# ATmega16A.net
KiCad netlist of a schematic drawn in EAGLE
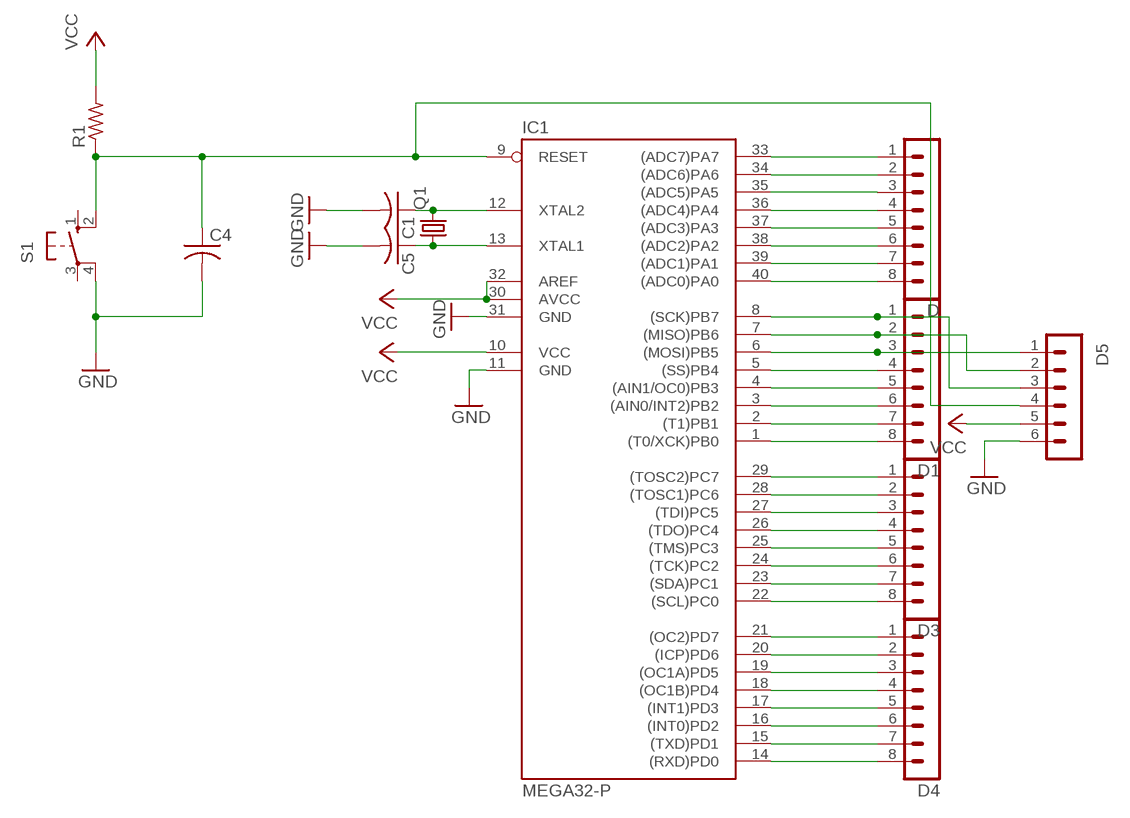
[diagram p0: schematic, sheet 1]

(export (version "E")
  (design (tool "Eeschema 10.0.6"))
  (components
    (comp (ref "C1")
      (value "C-US025-025X050")
      (footprint "eagle-import:C025-025X050")
      (libsource (lib "eagle-import") (part "C-US025-025X050"))
    )
    (comp (ref "C4")
      (value "C-US025-025X050")
      (footprint "eagle-import:C025-025X050")
      (libsource (lib "eagle-import") (part "C-US025-025X050"))
    )
    (comp (ref "C5")
      (value "C-US025-025X050")
      (footprint "eagle-import:C025-025X050")
      (libsource (lib "eagle-import") (part "C-US025-025X050"))
    )
    (comp (ref "D")
      (value "MA08-1")
      (footprint "eagle-import:MA08-1")
      (libsource (lib "eagle-import") (part "MA08-1"))
    )
    (comp (ref "D1")
      (value "MA08-1")
      (footprint "eagle-import:MA08-1")
      (libsource (lib "eagle-import") (part "MA08-1"))
    )
    (comp (ref "D3")
      (value "MA08-1")
      (footprint "eagle-import:MA08-1")
      (libsource (lib "eagle-import") (part "MA08-1"))
    )
    (comp (ref "D4")
      (value "MA08-1")
      (footprint "eagle-import:MA08-1")
      (libsource (lib "eagle-import") (part "MA08-1"))
    )
    (comp (ref "D5")
      (value "MA06-1")
      (footprint "eagle-import:MA06-1")
      (libsource (lib "eagle-import") (part "MA06-1"))
    )
    (comp (ref "IC1")
      (value "MEGA32-P")
      (footprint "eagle-import:DIL40")
      (fields (field (name "MPN") "ATMEGA32-16PU"))
      (libsource (lib "eagle-import") (part "MEGA32-P"))
    )
    (comp (ref "Q1")
      (value "CRYSTALHC49S")
      (footprint "eagle-import:HC49_S")
      (libsource (lib "eagle-import") (part "CRYSTALHC49S"))
    )
    (comp (ref "R1")
      (value "R-US_0204/7")
      (footprint "eagle-import:0204_7")
      (libsource (lib "eagle-import") (part "R-US_0204/7"))
    )
    (comp (ref "S1")
      (value "10-XX")
      (footprint "eagle-import:B3F-10XX")
      (fields (field (name "MPN") "B3F-1000"))
      (libsource (lib "eagle-import") (part "10-XX"))
    )
  )
  (nets
    (net (code "1") (name "GND") (class "Default")
      (node (ref "C1") (pin "2") (pinfunction "2_2") (pintype "passive"))
      (node (ref "C4") (pin "2") (pinfunction "2_2") (pintype "passive"))
      (node (ref "C5") (pin "2") (pinfunction "2_2") (pintype "passive"))
      (node (ref "D5") (pin "6") (pinfunction "6_6") (pintype "passive"))
      (node (ref "IC1") (pin "11") (pinfunction "GND_11") (pintype "power_in"))
      (node (ref "IC1") (pin "31") (pinfunction "GND_31") (pintype "power_in"))
      (node (ref "S1") (pin "4") (pinfunction "P1_4") (pintype "passive"))
    )
    (net (code "2") (name "Net-(IC1-(ADC0)PA0)") (class "Default")
      (node (ref "D") (pin "8") (pinfunction "8_8") (pintype "passive"))
      (node (ref "IC1") (pin "40") (pinfunction "(ADC0)PA0_40") (pintype "bidirectional"))
    )
    (net (code "3") (name "Net-(IC1-(ADC1)PA1)") (class "Default")
      (node (ref "D") (pin "7") (pinfunction "7_7") (pintype "passive"))
      (node (ref "IC1") (pin "39") (pinfunction "(ADC1)PA1_39") (pintype "bidirectional"))
    )
    (net (code "4") (name "Net-(IC1-(ADC2)PA2)") (class "Default")
      (node (ref "D") (pin "6") (pinfunction "6_6") (pintype "passive"))
      (node (ref "IC1") (pin "38") (pinfunction "(ADC2)PA2_38") (pintype "bidirectional"))
    )
    (net (code "5") (name "Net-(IC1-(ADC3)PA3)") (class "Default")
      (node (ref "D") (pin "5") (pinfunction "5_5") (pintype "passive"))
      (node (ref "IC1") (pin "37") (pinfunction "(ADC3)PA3_37") (pintype "bidirectional"))
    )
    (net (code "6") (name "Net-(IC1-(ADC4)PA4)") (class "Default")
      (node (ref "D") (pin "4") (pinfunction "4_4") (pintype "passive"))
      (node (ref "IC1") (pin "36") (pinfunction "(ADC4)PA4_36") (pintype "bidirectional"))
    )
    (net (code "7") (name "Net-(IC1-(ADC5)PA5)") (class "Default")
      (node (ref "D") (pin "3") (pinfunction "3_3") (pintype "passive"))
      (node (ref "IC1") (pin "35") (pinfunction "(ADC5)PA5_35") (pintype "bidirectional"))
    )
    (net (code "8") (name "Net-(IC1-(ADC6)PA6)") (class "Default")
      (node (ref "D") (pin "2") (pinfunction "2_2") (pintype "passive"))
      (node (ref "IC1") (pin "34") (pinfunction "(ADC6)PA6_34") (pintype "bidirectional"))
    )
    (net (code "9") (name "Net-(IC1-(ADC7)PA7)") (class "Default")
      (node (ref "D") (pin "1") (pinfunction "1_1") (pintype "passive"))
      (node (ref "IC1") (pin "33") (pinfunction "(ADC7)PA7_33") (pintype "bidirectional"))
    )
    (net (code "10") (name "Net-(IC1-(AIN0{slash}INT2)PB2)") (class "Default")
      (node (ref "D1") (pin "6") (pinfunction "6_6") (pintype "passive"))
      (node (ref "IC1") (pin "3") (pinfunction "(AIN0/INT2)PB2_3") (pintype "bidirectional"))
    )
    (net (code "11") (name "Net-(IC1-(AIN1{slash}OC0)PB3)") (class "Default")
      (node (ref "D1") (pin "5") (pinfunction "5_5") (pintype "passive"))
      (node (ref "IC1") (pin "4") (pinfunction "(AIN1/OC0)PB3_4") (pintype "bidirectional"))
    )
    (net (code "12") (name "Net-(IC1-(ICP)PD6)") (class "Default")
      (node (ref "D4") (pin "2") (pinfunction "2_2") (pintype "passive"))
      (node (ref "IC1") (pin "20") (pinfunction "(ICP)PD6_20") (pintype "bidirectional"))
    )
    (net (code "13") (name "Net-(IC1-(INT0)PD2)") (class "Default")
      (node (ref "D4") (pin "6") (pinfunction "6_6") (pintype "passive"))
      (node (ref "IC1") (pin "16") (pinfunction "(INT0)PD2_16") (pintype "bidirectional"))
    )
    (net (code "14") (name "Net-(IC1-(INT1)PD3)") (class "Default")
      (node (ref "D4") (pin "5") (pinfunction "5_5") (pintype "passive"))
      (node (ref "IC1") (pin "17") (pinfunction "(INT1)PD3_17") (pintype "bidirectional"))
    )
    (net (code "15") (name "Net-(IC1-(MISO)PB6)") (class "Default")
      (node (ref "D1") (pin "2") (pinfunction "2_2") (pintype "passive"))
      (node (ref "D5") (pin "2") (pinfunction "2_2") (pintype "passive"))
      (node (ref "IC1") (pin "7") (pinfunction "(MISO)PB6_7") (pintype "bidirectional"))
    )
    (net (code "16") (name "Net-(IC1-(MOSI)PB5)") (class "Default")
      (node (ref "D1") (pin "3") (pinfunction "3_3") (pintype "passive"))
      (node (ref "D5") (pin "1") (pinfunction "1_1") (pintype "passive"))
      (node (ref "IC1") (pin "6") (pinfunction "(MOSI)PB5_6") (pintype "bidirectional"))
    )
    (net (code "17") (name "Net-(IC1-(OC1A)PD5)") (class "Default")
      (node (ref "D4") (pin "3") (pinfunction "3_3") (pintype "passive"))
      (node (ref "IC1") (pin "19") (pinfunction "(OC1A)PD5_19") (pintype "bidirectional"))
    )
    (net (code "18") (name "Net-(IC1-(OC1B)PD4)") (class "Default")
      (node (ref "D4") (pin "4") (pinfunction "4_4") (pintype "passive"))
      (node (ref "IC1") (pin "18") (pinfunction "(OC1B)PD4_18") (pintype "bidirectional"))
    )
    (net (code "19") (name "Net-(IC1-(OC2)PD7)") (class "Default")
      (node (ref "D4") (pin "1") (pinfunction "1_1") (pintype "passive"))
      (node (ref "IC1") (pin "21") (pinfunction "(OC2)PD7_21") (pintype "bidirectional"))
    )
    (net (code "20") (name "Net-(IC1-(RXD)PD0)") (class "Default")
      (node (ref "D4") (pin "8") (pinfunction "8_8") (pintype "passive"))
      (node (ref "IC1") (pin "14") (pinfunction "(RXD)PD0_14") (pintype "bidirectional"))
    )
    (net (code "21") (name "Net-(IC1-(SCK)PB7)") (class "Default")
      (node (ref "D1") (pin "1") (pinfunction "1_1") (pintype "passive"))
      (node (ref "D5") (pin "3") (pinfunction "3_3") (pintype "passive"))
      (node (ref "IC1") (pin "8") (pinfunction "(SCK)PB7_8") (pintype "bidirectional"))
    )
    (net (code "22") (name "Net-(IC1-(SCL)PC0)") (class "Default")
      (node (ref "D3") (pin "8") (pinfunction "8_8") (pintype "passive"))
      (node (ref "IC1") (pin "22") (pinfunction "(SCL)PC0_22") (pintype "bidirectional"))
    )
    (net (code "23") (name "Net-(IC1-(SDA)PC1)") (class "Default")
      (node (ref "D3") (pin "7") (pinfunction "7_7") (pintype "passive"))
      (node (ref "IC1") (pin "23") (pinfunction "(SDA)PC1_23") (pintype "bidirectional"))
    )
    (net (code "24") (name "Net-(IC1-(SS)PB4)") (class "Default")
      (node (ref "D1") (pin "4") (pinfunction "4_4") (pintype "passive"))
      (node (ref "IC1") (pin "5") (pinfunction "(SS)PB4_5") (pintype "bidirectional"))
    )
    (net (code "25") (name "Net-(IC1-(T0{slash}XCK)PB0)") (class "Default")
      (node (ref "D1") (pin "8") (pinfunction "8_8") (pintype "passive"))
      (node (ref "IC1") (pin "1") (pinfunction "(T0/XCK)PB0_1") (pintype "bidirectional"))
    )
    (net (code "26") (name "Net-(IC1-(T1)PB1)") (class "Default")
      (node (ref "D1") (pin "7") (pinfunction "7_7") (pintype "passive"))
      (node (ref "IC1") (pin "2") (pinfunction "(T1)PB1_2") (pintype "bidirectional"))
    )
    (net (code "27") (name "Net-(IC1-(TCK)PC2)") (class "Default")
      (node (ref "D3") (pin "6") (pinfunction "6_6") (pintype "passive"))
      (node (ref "IC1") (pin "24") (pinfunction "(TCK)PC2_24") (pintype "bidirectional"))
    )
    (net (code "28") (name "Net-(IC1-(TDI)PC5)") (class "Default")
      (node (ref "D3") (pin "3") (pinfunction "3_3") (pintype "passive"))
      (node (ref "IC1") (pin "27") (pinfunction "(TDI)PC5_27") (pintype "bidirectional"))
    )
    (net (code "29") (name "Net-(IC1-(TDO)PC4)") (class "Default")
      (node (ref "D3") (pin "4") (pinfunction "4_4") (pintype "passive"))
      (node (ref "IC1") (pin "26") (pinfunction "(TDO)PC4_26") (pintype "bidirectional"))
    )
    (net (code "30") (name "Net-(IC1-(TMS)PC3)") (class "Default")
      (node (ref "D3") (pin "5") (pinfunction "5_5") (pintype "passive"))
      (node (ref "IC1") (pin "25") (pinfunction "(TMS)PC3_25") (pintype "bidirectional"))
    )
    (net (code "31") (name "Net-(IC1-(TOSC1)PC6)") (class "Default")
      (node (ref "D3") (pin "2") (pinfunction "2_2") (pintype "passive"))
      (node (ref "IC1") (pin "28") (pinfunction "(TOSC1)PC6_28") (pintype "bidirectional"))
    )
    (net (code "32") (name "Net-(IC1-(TOSC2)PC7)") (class "Default")
      (node (ref "D3") (pin "1") (pinfunction "1_1") (pintype "passive"))
      (node (ref "IC1") (pin "29") (pinfunction "(TOSC2)PC7_29") (pintype "bidirectional"))
    )
    (net (code "33") (name "Net-(IC1-(TXD)PD1)") (class "Default")
      (node (ref "D4") (pin "7") (pinfunction "7_7") (pintype "passive"))
      (node (ref "IC1") (pin "15") (pinfunction "(TXD)PD1_15") (pintype "bidirectional"))
    )
    (net (code "34") (name "Net-(IC1-RESET)") (class "Default")
      (node (ref "C4") (pin "1") (pinfunction "1_1") (pintype "passive"))
      (node (ref "D5") (pin "4") (pinfunction "4_4") (pintype "passive"))
      (node (ref "IC1") (pin "9") (pinfunction "RESET_9") (pintype "input"))
      (node (ref "R1") (pin "1") (pinfunction "1_1") (pintype "passive"))
      (node (ref "S1") (pin "2") (pinfunction "S1_2") (pintype "passive"))
    )
    (net (code "35") (name "Net-(IC1-XTAL1)") (class "Default")
      (node (ref "C5") (pin "1") (pinfunction "1_1") (pintype "passive"))
      (node (ref "IC1") (pin "13") (pinfunction "XTAL1_13") (pintype "bidirectional"))
      (node (ref "Q1") (pin "1") (pinfunction "1_1") (pintype "passive"))
    )
    (net (code "36") (name "Net-(IC1-XTAL2)") (class "Default")
      (node (ref "C1") (pin "1") (pinfunction "1_1") (pintype "passive"))
      (node (ref "IC1") (pin "12") (pinfunction "XTAL2_12") (pintype "bidirectional"))
      (node (ref "Q1") (pin "2") (pinfunction "2_2") (pintype "passive"))
    )
    (net (code "37") (name "VCC") (class "Default")
      (node (ref "D5") (pin "5") (pinfunction "5_5") (pintype "passive"))
      (node (ref "IC1") (pin "10") (pinfunction "VCC_10") (pintype "power_in"))
      (node (ref "IC1") (pin "30") (pinfunction "AVCC_30") (pintype "power_in"))
      (node (ref "IC1") (pin "32") (pinfunction "AREF_32") (pintype "passive"))
      (node (ref "R1") (pin "2") (pinfunction "2_2") (pintype "passive"))
    )
    (net (code "38") (name "unconnected-(S1-P-Pad3)") (class "Default")
      (node (ref "S1") (pin "3") (pinfunction "P_3") (pintype "passive"))
    )
    (net (code "39") (name "unconnected-(S1-S-Pad1)") (class "Default")
      (node (ref "S1") (pin "1") (pinfunction "S_1") (pintype "passive"))
    )
  )
)
